# mother_board.net
KiCad netlist of a schematic drawn in EAGLE
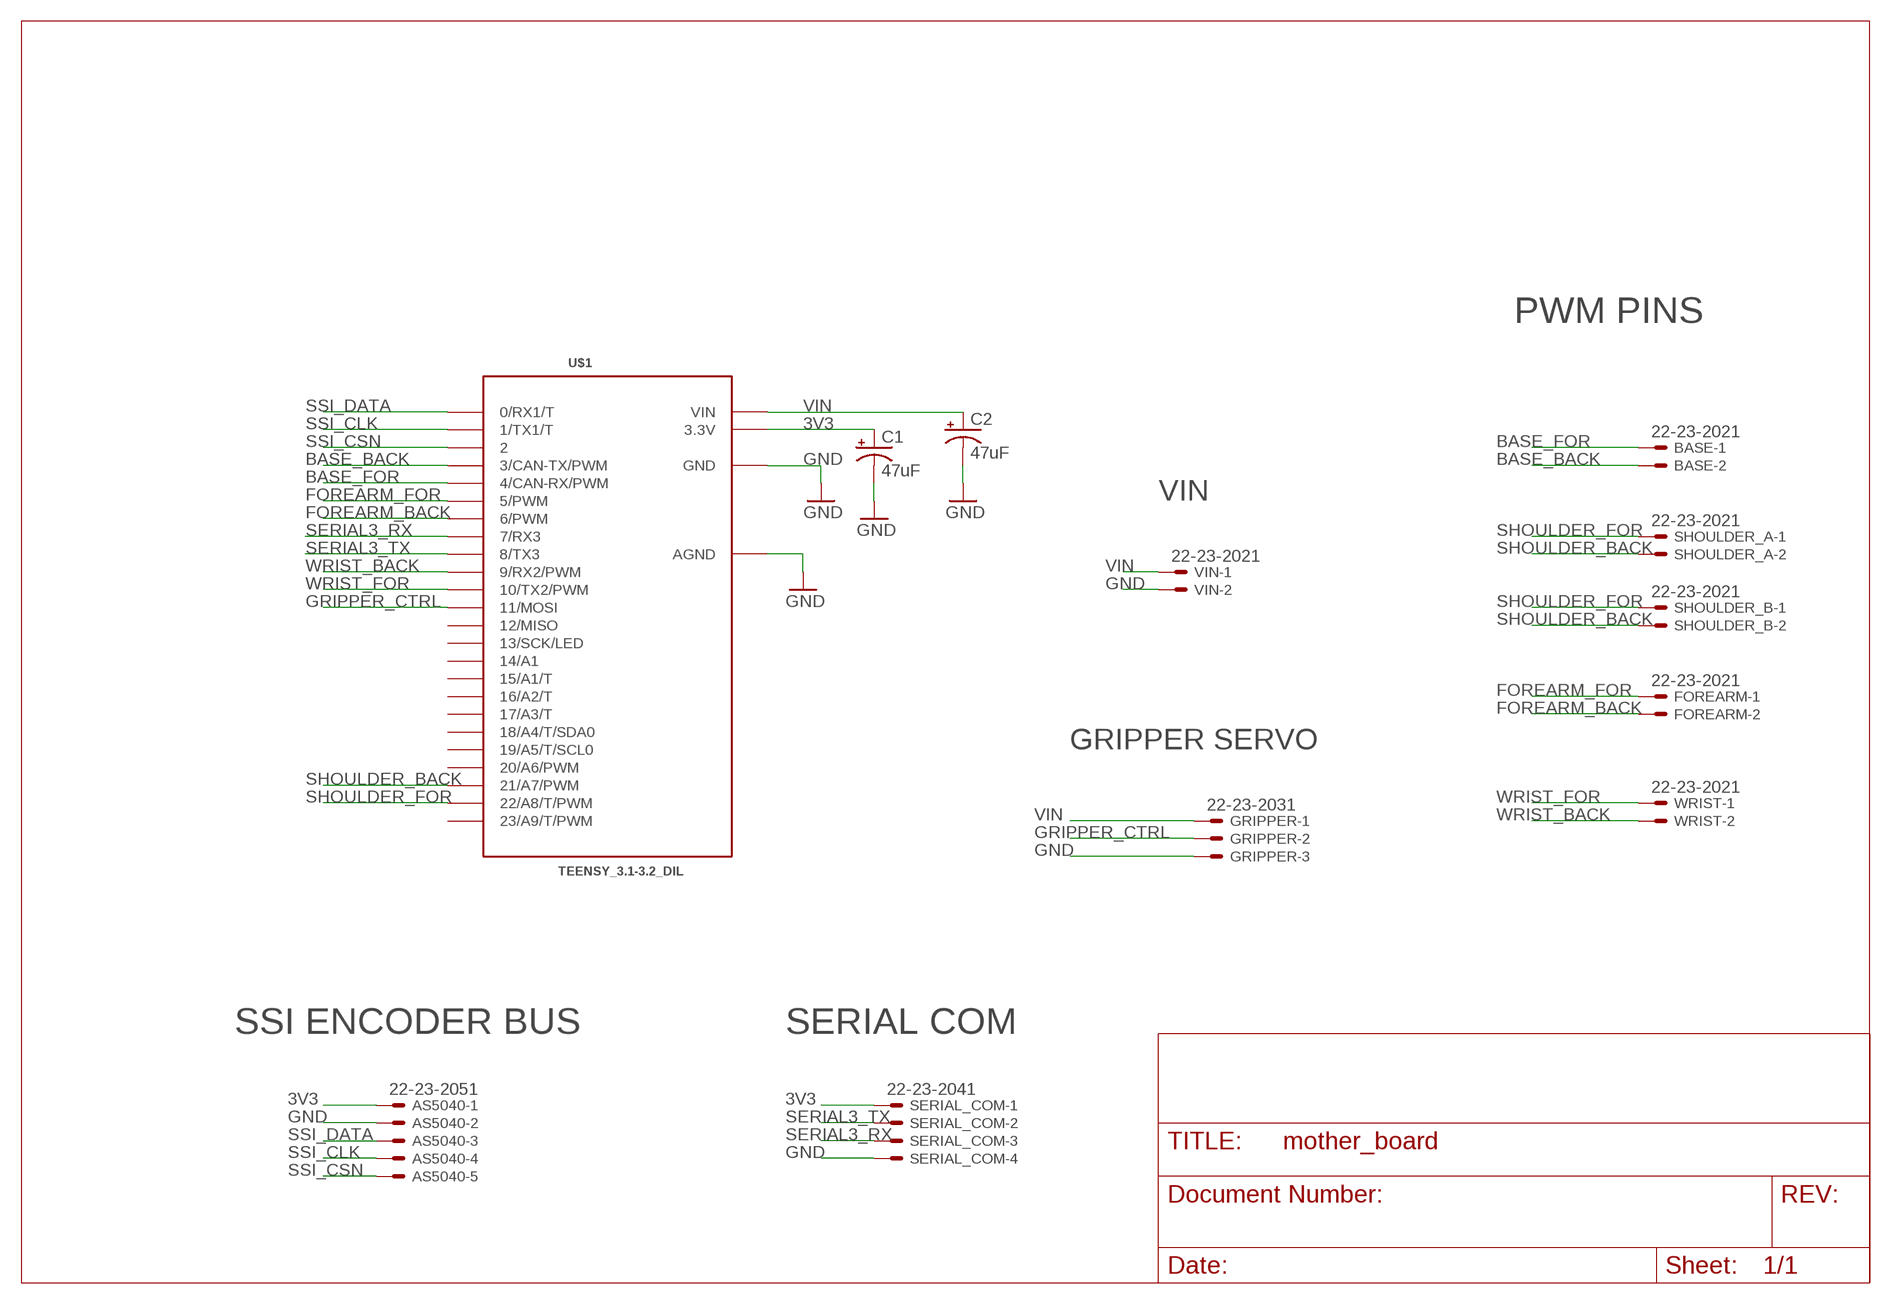
[diagram p0: schematic, sheet 1]

(export (version "E")
  (design (tool "Eeschema 10.0.6"))
  (components
    (comp (ref "AS5040")
      (value "22-23-2051")
      (footprint "eagle-import:22-23-2051")
      (fields (field (name "MF") "MOLEX"))
      (libsource (lib "eagle-import") (part "22-23-2051"))
    )
    (comp (ref "BASE")
      (value "22-23-2021")
      (footprint "eagle-import:22-23-2021")
      (fields (field (name "MF") "MOLEX"))
      (libsource (lib "eagle-import") (part "22-23-2021"))
    )
    (comp (ref "C1")
      (value "47uF")
      (footprint "eagle-import:E2,5-7")
      (libsource (lib "eagle-import") (part "CPOL-USE2.5-7"))
    )
    (comp (ref "C2")
      (value "47uF")
      (footprint "eagle-import:E2,5-7")
      (libsource (lib "eagle-import") (part "CPOL-USE2.5-7"))
    )
    (comp (ref "FOREARM")
      (value "22-23-2021")
      (footprint "eagle-import:22-23-2021")
      (fields (field (name "MF") "MOLEX"))
      (libsource (lib "eagle-import") (part "22-23-2021"))
    )
    (comp (ref "GRIPPER")
      (value "22-23-2031")
      (footprint "eagle-import:22-23-2031")
      (fields (field (name "MF") "MOLEX"))
      (libsource (lib "eagle-import") (part "22-23-2031"))
    )
    (comp (ref "SERIAL_COM")
      (value "22-23-2041")
      (footprint "eagle-import:22-23-2041")
      (fields (field (name "MF") "MOLEX"))
      (libsource (lib "eagle-import") (part "22-23-2041"))
    )
    (comp (ref "SHOULDER_A")
      (value "22-23-2021")
      (footprint "eagle-import:22-23-2021")
      (fields (field (name "MF") "MOLEX"))
      (libsource (lib "eagle-import") (part "22-23-2021"))
    )
    (comp (ref "SHOULDER_B")
      (value "22-23-2021")
      (footprint "eagle-import:22-23-2021")
      (fields (field (name "MF") "MOLEX"))
      (libsource (lib "eagle-import") (part "22-23-2021"))
    )
    (comp (ref "U$1")
      (value "TEENSY_3.1-3.2_DIL")
      (footprint "eagle-import:TEENSY_3.0-3.2&LC_DIL")
      (libsource (lib "eagle-import") (part "TEENSY_3.1-3.2_DIL"))
    )
    (comp (ref "VIN")
      (value "22-23-2021")
      (footprint "eagle-import:22-23-2021")
      (fields (field (name "MF") "MOLEX"))
      (libsource (lib "eagle-import") (part "22-23-2021"))
    )
    (comp (ref "WRIST")
      (value "22-23-2021")
      (footprint "eagle-import:22-23-2021")
      (fields (field (name "MF") "MOLEX"))
      (libsource (lib "eagle-import") (part "22-23-2021"))
    )
  )
  (nets
    (net (code "1") (name "/3V3") (class "Default")
      (node (ref "AS5040") (pin "1") (pinfunction "S_1") (pintype "passive"))
      (node (ref "C1") (pin "+") (pinfunction "+_+") (pintype "passive"))
      (node (ref "SERIAL_COM") (pin "1") (pinfunction "S_1") (pintype "passive"))
      (node (ref "U$1") (pin "3.3V") (pinfunction "3.3V_3.3V") (pintype "power_in"))
    )
    (net (code "2") (name "/BASE_BACK") (class "Default")
      (node (ref "BASE") (pin "2") (pinfunction "S_2") (pintype "passive"))
      (node (ref "U$1") (pin "3") (pinfunction "3/CAN-TX/PWM_3") (pintype "bidirectional"))
    )
    (net (code "3") (name "/BASE_FOR") (class "Default")
      (node (ref "BASE") (pin "1") (pinfunction "S_1") (pintype "passive"))
      (node (ref "U$1") (pin "4") (pinfunction "4/CAN-RX/PWM_4") (pintype "bidirectional"))
    )
    (net (code "4") (name "/FOREARM_BACK") (class "Default")
      (node (ref "FOREARM") (pin "2") (pinfunction "S_2") (pintype "passive"))
      (node (ref "U$1") (pin "6") (pinfunction "6/PWM_6") (pintype "bidirectional"))
    )
    (net (code "5") (name "/FOREARM_FOR") (class "Default")
      (node (ref "FOREARM") (pin "1") (pinfunction "S_1") (pintype "passive"))
      (node (ref "U$1") (pin "5") (pinfunction "5/PWM_5") (pintype "bidirectional"))
    )
    (net (code "6") (name "/GRIPPER_CTRL") (class "Default")
      (node (ref "GRIPPER") (pin "2") (pinfunction "S_2") (pintype "passive"))
      (node (ref "U$1") (pin "11") (pinfunction "11/MOSI_11") (pintype "bidirectional"))
    )
    (net (code "7") (name "/SERIAL3_RX") (class "Default")
      (node (ref "SERIAL_COM") (pin "3") (pinfunction "S_3") (pintype "passive"))
      (node (ref "U$1") (pin "7") (pinfunction "7/RX3_7") (pintype "bidirectional"))
    )
    (net (code "8") (name "/SERIAL3_TX") (class "Default")
      (node (ref "SERIAL_COM") (pin "2") (pinfunction "S_2") (pintype "passive"))
      (node (ref "U$1") (pin "8") (pinfunction "8/TX3_8") (pintype "bidirectional"))
    )
    (net (code "9") (name "/SHOULDER_BACK") (class "Default")
      (node (ref "SHOULDER_A") (pin "2") (pinfunction "S_2") (pintype "passive"))
      (node (ref "SHOULDER_B") (pin "2") (pinfunction "S_2") (pintype "passive"))
      (node (ref "U$1") (pin "21/A7") (pinfunction "21/A7/PWM_21/A7") (pintype "bidirectional"))
    )
    (net (code "10") (name "/SHOULDER_FOR") (class "Default")
      (node (ref "SHOULDER_A") (pin "1") (pinfunction "S_1") (pintype "passive"))
      (node (ref "SHOULDER_B") (pin "1") (pinfunction "S_1") (pintype "passive"))
      (node (ref "U$1") (pin "22/A8") (pinfunction "22/A8/T/PWM_22/A8") (pintype "bidirectional"))
    )
    (net (code "11") (name "/SSI_CLK") (class "Default")
      (node (ref "AS5040") (pin "4") (pinfunction "S_4") (pintype "passive"))
      (node (ref "U$1") (pin "1") (pinfunction "1/TX1/T_1") (pintype "bidirectional"))
    )
    (net (code "12") (name "/SSI_CSN") (class "Default")
      (node (ref "AS5040") (pin "5") (pinfunction "S_5") (pintype "passive"))
      (node (ref "U$1") (pin "2") (pinfunction "2_2") (pintype "bidirectional"))
    )
    (net (code "13") (name "/SSI_DATA") (class "Default")
      (node (ref "AS5040") (pin "3") (pinfunction "S_3") (pintype "passive"))
      (node (ref "U$1") (pin "0") (pinfunction "0/RX1/T_0") (pintype "bidirectional"))
    )
    (net (code "14") (name "/VIN") (class "Default")
      (node (ref "C2") (pin "+") (pinfunction "+_+") (pintype "passive"))
      (node (ref "GRIPPER") (pin "1") (pinfunction "S_1") (pintype "passive"))
      (node (ref "U$1") (pin "VIN") (pinfunction "VIN_VIN") (pintype "power_in"))
      (node (ref "VIN") (pin "1") (pinfunction "S_1") (pintype "passive"))
    )
    (net (code "15") (name "/WRIST_BACK") (class "Default")
      (node (ref "U$1") (pin "9") (pinfunction "9/RX2/PWM_9") (pintype "bidirectional"))
      (node (ref "WRIST") (pin "2") (pinfunction "S_2") (pintype "passive"))
    )
    (net (code "16") (name "/WRIST_FOR") (class "Default")
      (node (ref "U$1") (pin "10") (pinfunction "10/TX2/PWM_10") (pintype "bidirectional"))
      (node (ref "WRIST") (pin "1") (pinfunction "S_1") (pintype "passive"))
    )
    (net (code "17") (name "GND") (class "Default")
      (node (ref "AS5040") (pin "2") (pinfunction "S_2") (pintype "passive"))
      (node (ref "C1") (pin "-") (pinfunction "-_-") (pintype "passive"))
      (node (ref "C2") (pin "-") (pinfunction "-_-") (pintype "passive"))
      (node (ref "GRIPPER") (pin "3") (pinfunction "S_3") (pintype "passive"))
      (node (ref "SERIAL_COM") (pin "4") (pinfunction "S_4") (pintype "passive"))
      (node (ref "U$1") (pin "AGND") (pinfunction "AGND_AGND") (pintype "power_in"))
      (node (ref "U$1") (pin "GND") (pinfunction "GND_GND") (pintype "power_in"))
      (node (ref "VIN") (pin "2") (pinfunction "S_2") (pintype "passive"))
    )
    (net (code "18") (name "unconnected-(U$1-12{slash}MISO-Pad12)") (class "Default")
      (node (ref "U$1") (pin "12") (pinfunction "12/MISO_12") (pintype "bidirectional"))
    )
    (net (code "19") (name "unconnected-(U$1-13{slash}SCK{slash}LED-Pad13)") (class "Default")
      (node (ref "U$1") (pin "13") (pinfunction "13/SCK/LED_13") (pintype "bidirectional"))
    )
    (net (code "20") (name "unconnected-(U$1-14{slash}A1-Pad14{slash}A0)") (class "Default")
      (node (ref "U$1") (pin "14/A0") (pinfunction "14/A1_14/A0") (pintype "bidirectional"))
    )
    (net (code "21") (name "unconnected-(U$1-15{slash}A1{slash}T-Pad15{slash}A1)") (class "Default")
      (node (ref "U$1") (pin "15/A1") (pinfunction "15/A1/T_15/A1") (pintype "bidirectional"))
    )
    (net (code "22") (name "unconnected-(U$1-16{slash}A2{slash}T-Pad16{slash}A2)") (class "Default")
      (node (ref "U$1") (pin "16/A2") (pinfunction "16/A2/T_16/A2") (pintype "bidirectional"))
    )
    (net (code "23") (name "unconnected-(U$1-17{slash}A3{slash}T-Pad17{slash}A3)") (class "Default")
      (node (ref "U$1") (pin "17/A3") (pinfunction "17/A3/T_17/A3") (pintype "bidirectional"))
    )
    (net (code "24") (name "unconnected-(U$1-18{slash}A4{slash}T{slash}SDA0-Pad18{slash}A4)") (class "Default")
      (node (ref "U$1") (pin "18/A4") (pinfunction "18/A4/T/SDA0_18/A4") (pintype "bidirectional"))
    )
    (net (code "25") (name "unconnected-(U$1-19{slash}A5{slash}T{slash}SCL0-Pad19{slash}A5)") (class "Default")
      (node (ref "U$1") (pin "19/A5") (pinfunction "19/A5/T/SCL0_19/A5") (pintype "bidirectional"))
    )
    (net (code "26") (name "unconnected-(U$1-20{slash}A6{slash}PWM-Pad20{slash}A6)") (class "Default")
      (node (ref "U$1") (pin "20/A6") (pinfunction "20/A6/PWM_20/A6") (pintype "bidirectional"))
    )
    (net (code "27") (name "unconnected-(U$1-23{slash}A9{slash}T{slash}PWM-Pad23{slash}A9)") (class "Default")
      (node (ref "U$1") (pin "23/A9") (pinfunction "23/A9/T/PWM_23/A9") (pintype "bidirectional"))
    )
  )
)
